# BeebOPL.net
KiCad netlist of a schematic drawn in EAGLE
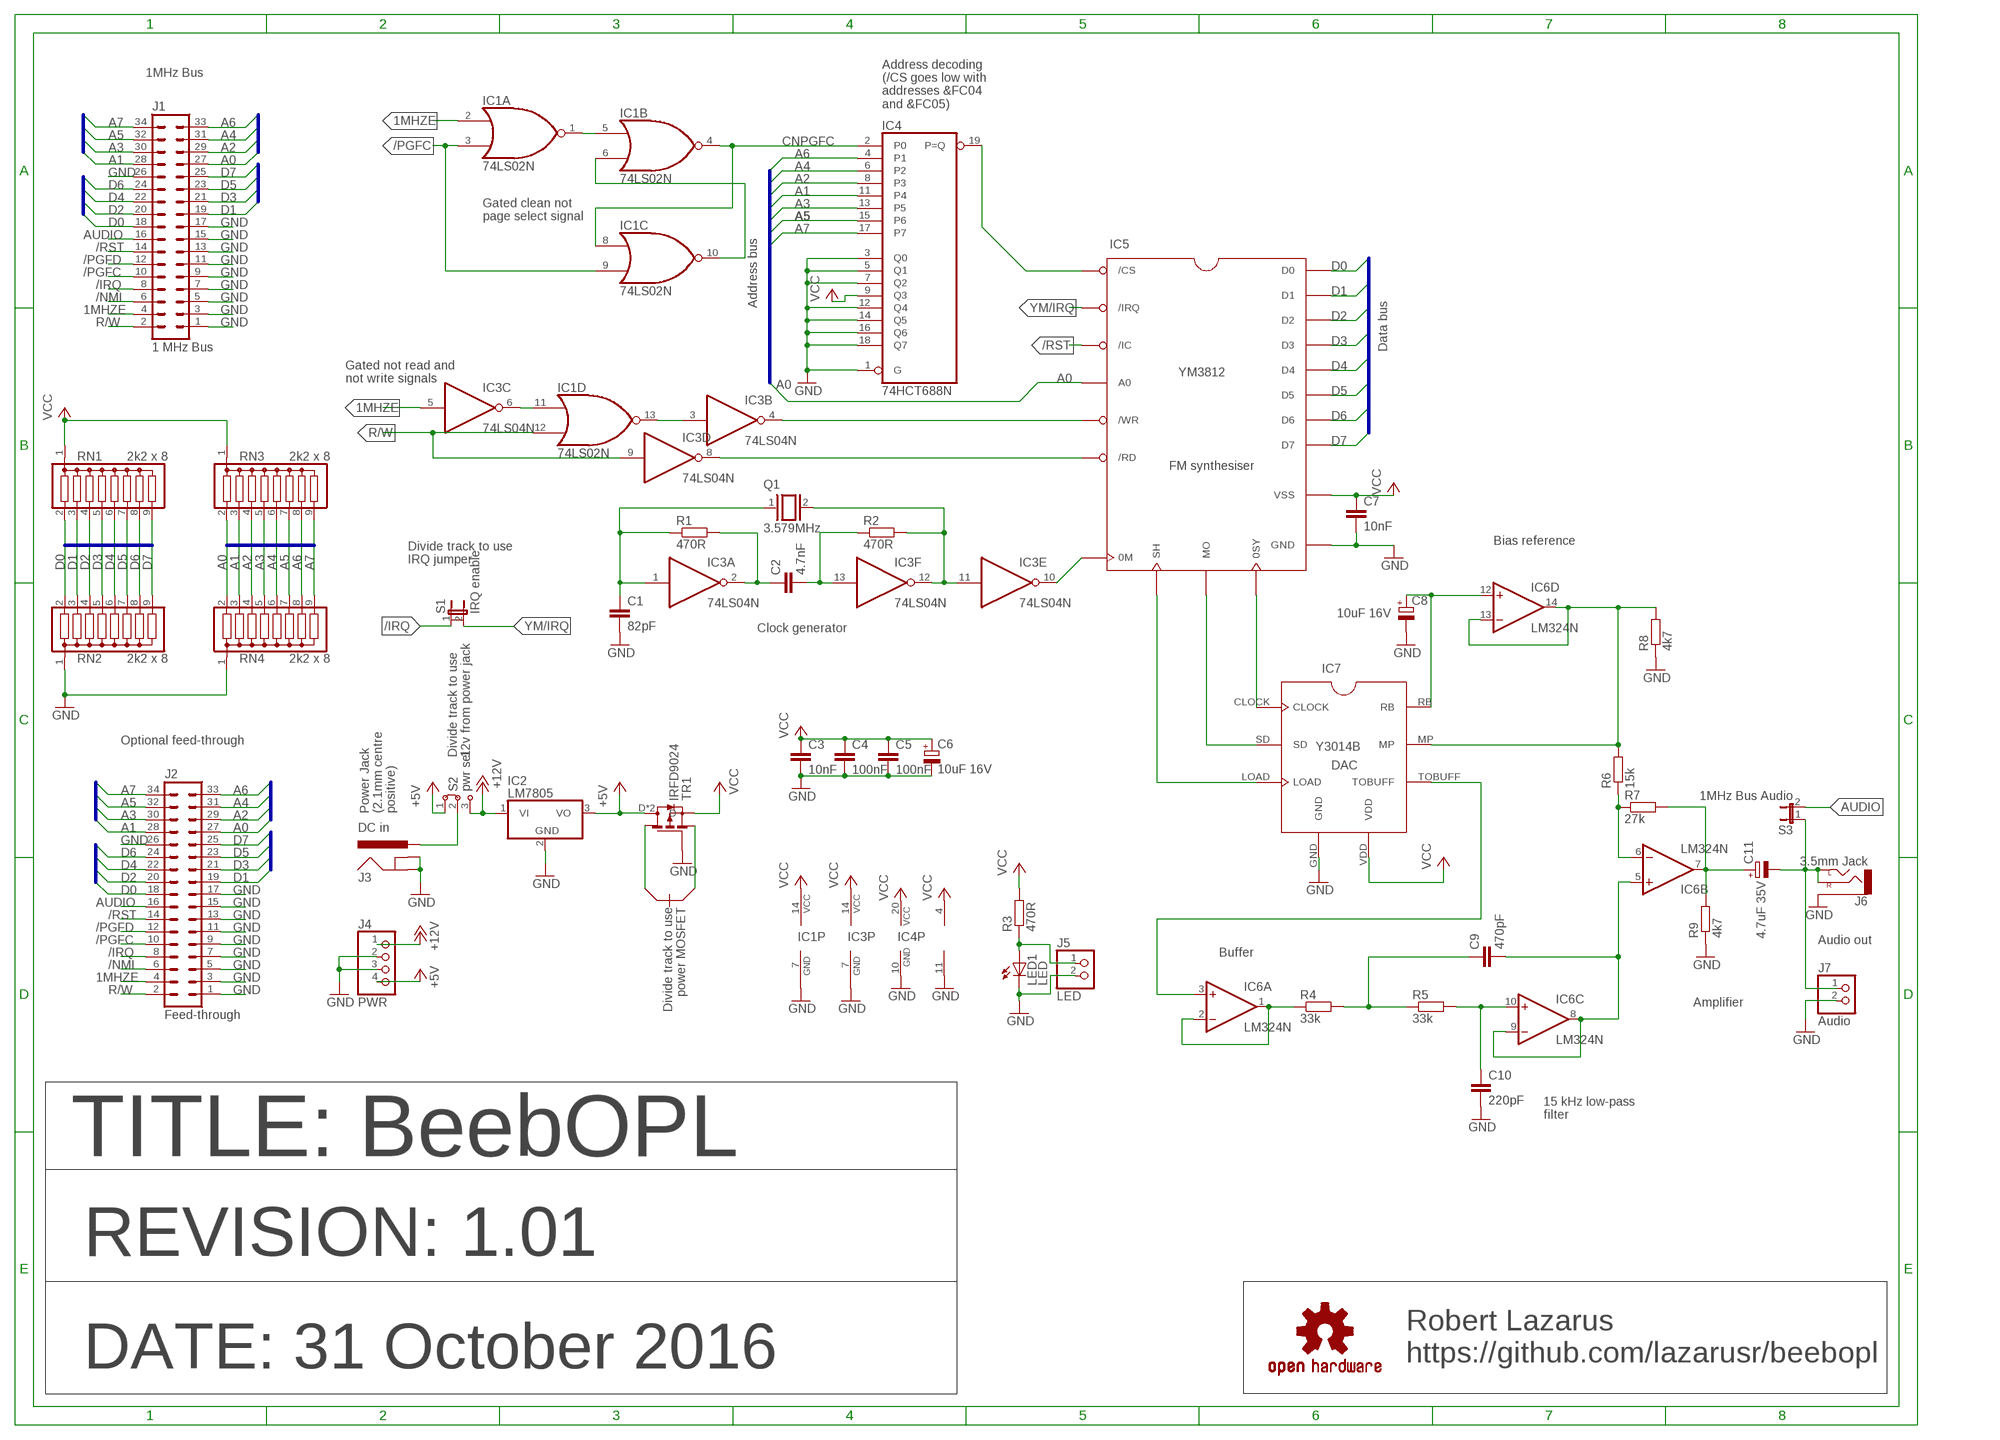
[diagram p0: schematic, sheet 1]

(export (version "E")
  (design (tool "Eeschema 10.0.6"))
  (components
    (comp (ref "C1")
      (value "82pF")
      (footprint "eagle-import:C050-024X044")
      (libsource (lib "eagle-import") (part "C-EU050-024X044"))
    )
    (comp (ref "C2")
      (value "4.7nF")
      (footprint "eagle-import:C050-024X044")
      (libsource (lib "eagle-import") (part "C-EU050-024X044"))
    )
    (comp (ref "C3")
      (value "10nF")
      (footprint "eagle-import:C050-024X044")
      (libsource (lib "eagle-import") (part "C-EU050-024X044"))
    )
    (comp (ref "C4")
      (value "100nF")
      (footprint "eagle-import:C050-024X044")
      (libsource (lib "eagle-import") (part "C-EU050-024X044"))
    )
    (comp (ref "C5")
      (value "100nF")
      (footprint "eagle-import:C050-024X044")
      (libsource (lib "eagle-import") (part "C-EU050-024X044"))
    )
    (comp (ref "C6")
      (value "10uF 16V")
      (footprint "eagle-import:E2,5-5")
      (libsource (lib "eagle-import") (part "CPOL-EUE2.5-5"))
    )
    (comp (ref "C7")
      (value "10nF")
      (footprint "eagle-import:C050-024X044")
      (libsource (lib "eagle-import") (part "C-EU050-024X044"))
    )
    (comp (ref "C8")
      (value "10uF 16V")
      (footprint "eagle-import:E2,5-5")
      (libsource (lib "eagle-import") (part "CPOL-EUE2.5-5"))
    )
    (comp (ref "C9")
      (value "470pF")
      (footprint "eagle-import:C050-024X044")
      (libsource (lib "eagle-import") (part "C-EU050-024X044"))
    )
    (comp (ref "C10")
      (value "220pF")
      (footprint "eagle-import:C050-024X044")
      (libsource (lib "eagle-import") (part "C-EU050-024X044"))
    )
    (comp (ref "C11")
      (value "4.7uF 35V")
      (footprint "eagle-import:E2,5-5")
      (libsource (lib "eagle-import") (part "CPOL-EUE2.5-5"))
    )
    (comp (ref "IC1")
      (value "74LS02N")
      (footprint "eagle-import:DIL14")
      (libsource (lib "eagle-import") (part "7402NLS"))
    )
    (comp (ref "IC2")
      (value "LM7805")
      (footprint "eagle-import:TO220V")
      (libsource (lib "eagle-import") (part "78TV05"))
    )
    (comp (ref "IC3")
      (value "74LS04N")
      (footprint "eagle-import:DIL14")
      (libsource (lib "eagle-import") (part "7404NLS"))
    )
    (comp (ref "IC4")
      (value "74HCT688N")
      (footprint "eagle-import:DIL20")
      (libsource (lib "eagle-import") (part "74688NHCT"))
    )
    (comp (ref "IC5")
      (value "YM3812")
      (footprint "eagle-import:YM3812")
      (libsource (lib "eagle-import") (part "YM3812-DIP24"))
    )
    (comp (ref "IC6")
      (value "LM324N")
      (footprint "eagle-import:DIL14")
      (libsource (lib "eagle-import") (part "LM324N"))
    )
    (comp (ref "IC7")
      (value "Y3014B")
      (footprint "eagle-import:YM3014B")
      (libsource (lib "eagle-import") (part "YM3014B-DIP8"))
    )
    (comp (ref "J1")
      (value "1 MHz Bus")
      (footprint "eagle-import:ML34")
      (libsource (lib "eagle-import") (part "ML34"))
    )
    (comp (ref "J2")
      (value "Feed-through")
      (footprint "eagle-import:ML34")
      (libsource (lib "eagle-import") (part "ML34"))
    )
    (comp (ref "J3")
      (value "DC in")
      (footprint "eagle-import:POWER_JACK_SLOT")
      (libsource (lib "eagle-import") (part "POWER_JACKSLT"))
    )
    (comp (ref "J4")
      (value "PWR")
      (footprint "eagle-import:1X04")
      (libsource (lib "eagle-import") (part "PINHD-1X4"))
    )
    (comp (ref "J5")
      (value "LED")
      (footprint "eagle-import:1X02")
      (libsource (lib "eagle-import") (part "PINHD-1X2"))
    )
    (comp (ref "J6")
      (value "3.5mm Jack")
      (footprint "eagle-import:AUDIO-JACK")
      (libsource (lib "eagle-import") (part "AUDIO-JACKPTH"))
    )
    (comp (ref "J7")
      (value "Audio")
      (footprint "eagle-import:1X02")
      (libsource (lib "eagle-import") (part "PINHD-1X2"))
    )
    (comp (ref "LED1")
      (value "LED")
      (footprint "eagle-import:LED5MM")
      (libsource (lib "eagle-import") (part "LED5MM"))
    )
    (comp (ref "LOGO1")
      (value "OSHW-LOGO-BOTTOML")
      (footprint "eagle-import:OSHW-LOGO-L")
      (libsource (lib "eagle-import") (part "OSHW-LOGO-BOTTOML"))
    )
    (comp (ref "Q1")
      (value "3.579MHz")
      (footprint "eagle-import:QS")
      (libsource (lib "eagle-import") (part "XTAL/S"))
    )
    (comp (ref "R1")
      (value "470R")
      (footprint "eagle-import:0207_10")
      (libsource (lib "eagle-import") (part "R-EU_0207/10"))
    )
    (comp (ref "R2")
      (value "470R")
      (footprint "eagle-import:0207_10")
      (libsource (lib "eagle-import") (part "R-EU_0207/10"))
    )
    (comp (ref "R3")
      (value "470R")
      (footprint "eagle-import:0207_10")
      (libsource (lib "eagle-import") (part "R-EU_0207/10"))
    )
    (comp (ref "R4")
      (value "33k")
      (footprint "eagle-import:0207_10")
      (libsource (lib "eagle-import") (part "R-EU_0207/10"))
    )
    (comp (ref "R5")
      (value "33k")
      (footprint "eagle-import:0207_10")
      (libsource (lib "eagle-import") (part "R-EU_0207/10"))
    )
    (comp (ref "R6")
      (value "15k")
      (footprint "eagle-import:0207_10")
      (libsource (lib "eagle-import") (part "R-EU_0207/10"))
    )
    (comp (ref "R7")
      (value "27k")
      (footprint "eagle-import:0207_10")
      (libsource (lib "eagle-import") (part "R-EU_0207/10"))
    )
    (comp (ref "R8")
      (value "4k7")
      (footprint "eagle-import:0207_10")
      (libsource (lib "eagle-import") (part "R-EU_0207/10"))
    )
    (comp (ref "R9")
      (value "4k7")
      (footprint "eagle-import:0207_10")
      (libsource (lib "eagle-import") (part "R-EU_0207/10"))
    )
    (comp (ref "RN1")
      (value "2k2 x 8")
      (footprint "eagle-import:SIL9")
      (libsource (lib "eagle-import") (part "G08R"))
    )
    (comp (ref "RN2")
      (value "2k2 x 8")
      (footprint "eagle-import:SIL9")
      (libsource (lib "eagle-import") (part "G08R"))
    )
    (comp (ref "RN3")
      (value "2k2 x 8")
      (footprint "eagle-import:SIL9")
      (libsource (lib "eagle-import") (part "G08R"))
    )
    (comp (ref "RN4")
      (value "2k2 x 8")
      (footprint "eagle-import:SIL9")
      (libsource (lib "eagle-import") (part "G08R"))
    )
    (comp (ref "S1")
      (value "IRQ enable")
      (footprint "eagle-import:1X02")
      (libsource (lib "eagle-import") (part "YMSynth_JUMPER-2PTH"))
    )
    (comp (ref "S2")
      (value "pwr sel")
      (footprint "eagle-import:S_3WAY_OR")
      (libsource (lib "eagle-import") (part "J2"))
    )
    (comp (ref "S3")
      (value "1MHz Bus Audio")
      (footprint "eagle-import:1X02")
      (libsource (lib "eagle-import") (part "JUMPER-2PTH"))
    )
    (comp (ref "TR1")
      (value "IRFD9024")
      (footprint "eagle-import:FET-DIL-OPTN")
      (libsource (lib "eagle-import") (part "IRFD9024-OPTN"))
    )
  )
  (nets
    (net (code "1") (name "+5V") (class "Default")
      (node (ref "IC2") (pin "3") (pinfunction "VO_3") (pintype "passive"))
      (node (ref "J4") (pin "4") (pinfunction "4_4") (pintype "passive"))
      (node (ref "S2") (pin "1") (pinfunction "1_1") (pintype "passive"))
      (node (ref "TR1") (pin "D") (pinfunction "D_D") (pintype "passive"))
      (node (ref "TR1") (pin "D1") (pinfunction "D_D1") (pintype "passive"))
    )
    (net (code "2") (name "+12V") (class "Default")
      (node (ref "IC2") (pin "1") (pinfunction "VI_1") (pintype "input"))
      (node (ref "J4") (pin "1") (pinfunction "1_1") (pintype "passive"))
      (node (ref "S2") (pin "3") (pinfunction "3_3") (pintype "passive"))
    )
    (net (code "3") (name "/A0") (class "Default")
      (node (ref "IC5") (pin "A0") (pinfunction "A0_A0") (pintype "bidirectional"))
      (node (ref "J1") (pin "27") (pinfunction "27_27") (pintype "passive"))
      (node (ref "J2") (pin "27") (pinfunction "27_27") (pintype "passive"))
      (node (ref "RN3") (pin "2") (pinfunction "2_2") (pintype "passive"))
      (node (ref "RN4") (pin "2") (pinfunction "2_2") (pintype "passive"))
    )
    (net (code "4") (name "/A1") (class "Default")
      (node (ref "IC4") (pin "11") (pinfunction "P4_11") (pintype "input"))
      (node (ref "J1") (pin "28") (pinfunction "28_28") (pintype "passive"))
      (node (ref "J2") (pin "28") (pinfunction "28_28") (pintype "passive"))
      (node (ref "RN3") (pin "3") (pinfunction "3_3") (pintype "passive"))
      (node (ref "RN4") (pin "3") (pinfunction "3_3") (pintype "passive"))
    )
    (net (code "5") (name "/A2") (class "Default")
      (node (ref "IC4") (pin "8") (pinfunction "P3_8") (pintype "input"))
      (node (ref "J1") (pin "29") (pinfunction "29_29") (pintype "passive"))
      (node (ref "J2") (pin "29") (pinfunction "29_29") (pintype "passive"))
      (node (ref "RN3") (pin "4") (pinfunction "4_4") (pintype "passive"))
      (node (ref "RN4") (pin "4") (pinfunction "4_4") (pintype "passive"))
    )
    (net (code "6") (name "/A3") (class "Default")
      (node (ref "IC4") (pin "13") (pinfunction "P5_13") (pintype "input"))
      (node (ref "J1") (pin "30") (pinfunction "30_30") (pintype "passive"))
      (node (ref "J2") (pin "30") (pinfunction "30_30") (pintype "passive"))
      (node (ref "RN3") (pin "5") (pinfunction "5_5") (pintype "passive"))
      (node (ref "RN4") (pin "5") (pinfunction "5_5") (pintype "passive"))
    )
    (net (code "7") (name "/A4") (class "Default")
      (node (ref "IC4") (pin "6") (pinfunction "P2_6") (pintype "input"))
      (node (ref "J1") (pin "31") (pinfunction "31_31") (pintype "passive"))
      (node (ref "J2") (pin "31") (pinfunction "31_31") (pintype "passive"))
      (node (ref "RN3") (pin "6") (pinfunction "6_6") (pintype "passive"))
      (node (ref "RN4") (pin "6") (pinfunction "6_6") (pintype "passive"))
    )
    (net (code "8") (name "/A5") (class "Default")
      (node (ref "IC4") (pin "15") (pinfunction "P6_15") (pintype "input"))
      (node (ref "J1") (pin "32") (pinfunction "32_32") (pintype "passive"))
      (node (ref "J2") (pin "32") (pinfunction "32_32") (pintype "passive"))
      (node (ref "RN3") (pin "7") (pinfunction "7_7") (pintype "passive"))
      (node (ref "RN4") (pin "7") (pinfunction "7_7") (pintype "passive"))
    )
    (net (code "9") (name "/A6") (class "Default")
      (node (ref "IC4") (pin "4") (pinfunction "P1_4") (pintype "input"))
      (node (ref "J1") (pin "33") (pinfunction "33_33") (pintype "passive"))
      (node (ref "J2") (pin "33") (pinfunction "33_33") (pintype "passive"))
      (node (ref "RN3") (pin "8") (pinfunction "8_8") (pintype "passive"))
      (node (ref "RN4") (pin "8") (pinfunction "8_8") (pintype "passive"))
    )
    (net (code "10") (name "/A7") (class "Default")
      (node (ref "IC4") (pin "17") (pinfunction "P7_17") (pintype "input"))
      (node (ref "J1") (pin "34") (pinfunction "34_34") (pintype "passive"))
      (node (ref "J2") (pin "34") (pinfunction "34_34") (pintype "passive"))
      (node (ref "RN3") (pin "9") (pinfunction "9_9") (pintype "passive"))
      (node (ref "RN4") (pin "9") (pinfunction "9_9") (pintype "passive"))
    )
    (net (code "11") (name "/CNPGFC") (class "Default")
      (node (ref "IC1") (pin "4") (pinfunction "O_4") (pintype "output"))
      (node (ref "IC1") (pin "8") (pinfunction "I0_8") (pintype "input"))
      (node (ref "IC4") (pin "2") (pinfunction "P0_2") (pintype "input"))
    )
    (net (code "12") (name "/D0") (class "Default")
      (node (ref "IC5") (pin "D0") (pinfunction "D0_D0") (pintype "power_in"))
      (node (ref "J1") (pin "18") (pinfunction "18_18") (pintype "passive"))
      (node (ref "J2") (pin "18") (pinfunction "18_18") (pintype "passive"))
      (node (ref "RN1") (pin "2") (pinfunction "2_2") (pintype "passive"))
      (node (ref "RN2") (pin "2") (pinfunction "2_2") (pintype "passive"))
    )
    (net (code "13") (name "/D1") (class "Default")
      (node (ref "IC5") (pin "D1") (pinfunction "D1_D1") (pintype "power_in"))
      (node (ref "J1") (pin "19") (pinfunction "19_19") (pintype "passive"))
      (node (ref "J2") (pin "19") (pinfunction "19_19") (pintype "passive"))
      (node (ref "RN1") (pin "3") (pinfunction "3_3") (pintype "passive"))
      (node (ref "RN2") (pin "3") (pinfunction "3_3") (pintype "passive"))
    )
    (net (code "14") (name "/D2") (class "Default")
      (node (ref "IC5") (pin "D2") (pinfunction "D2_D2") (pintype "power_in"))
      (node (ref "J1") (pin "20") (pinfunction "20_20") (pintype "passive"))
      (node (ref "J2") (pin "20") (pinfunction "20_20") (pintype "passive"))
      (node (ref "RN1") (pin "4") (pinfunction "4_4") (pintype "passive"))
      (node (ref "RN2") (pin "4") (pinfunction "4_4") (pintype "passive"))
    )
    (net (code "15") (name "/D3") (class "Default")
      (node (ref "IC5") (pin "D3") (pinfunction "D3_D3") (pintype "power_in"))
      (node (ref "J1") (pin "21") (pinfunction "21_21") (pintype "passive"))
      (node (ref "J2") (pin "21") (pinfunction "21_21") (pintype "passive"))
      (node (ref "RN1") (pin "5") (pinfunction "5_5") (pintype "passive"))
      (node (ref "RN2") (pin "5") (pinfunction "5_5") (pintype "passive"))
    )
    (net (code "16") (name "/D4") (class "Default")
      (node (ref "IC5") (pin "D4") (pinfunction "D4_D4") (pintype "power_in"))
      (node (ref "J1") (pin "22") (pinfunction "22_22") (pintype "passive"))
      (node (ref "J2") (pin "22") (pinfunction "22_22") (pintype "passive"))
      (node (ref "RN1") (pin "6") (pinfunction "6_6") (pintype "passive"))
      (node (ref "RN2") (pin "6") (pinfunction "6_6") (pintype "passive"))
    )
    (net (code "17") (name "/D5") (class "Default")
      (node (ref "IC5") (pin "D5") (pinfunction "D5_D5") (pintype "power_in"))
      (node (ref "J1") (pin "23") (pinfunction "23_23") (pintype "passive"))
      (node (ref "J2") (pin "23") (pinfunction "23_23") (pintype "passive"))
      (node (ref "RN1") (pin "7") (pinfunction "7_7") (pintype "passive"))
      (node (ref "RN2") (pin "7") (pinfunction "7_7") (pintype "passive"))
    )
    (net (code "18") (name "/D6") (class "Default")
      (node (ref "IC5") (pin "D6") (pinfunction "D6_D6") (pintype "power_in"))
      (node (ref "J1") (pin "24") (pinfunction "24_24") (pintype "passive"))
      (node (ref "J2") (pin "24") (pinfunction "24_24") (pintype "passive"))
      (node (ref "RN1") (pin "8") (pinfunction "8_8") (pintype "passive"))
      (node (ref "RN2") (pin "8") (pinfunction "8_8") (pintype "passive"))
    )
    (net (code "19") (name "/D7") (class "Default")
      (node (ref "IC5") (pin "D7") (pinfunction "D7_D7") (pintype "power_in"))
      (node (ref "J1") (pin "25") (pinfunction "25_25") (pintype "passive"))
      (node (ref "J2") (pin "25") (pinfunction "25_25") (pintype "passive"))
      (node (ref "RN1") (pin "9") (pinfunction "9_9") (pintype "passive"))
      (node (ref "RN2") (pin "9") (pinfunction "9_9") (pintype "passive"))
    )
    (net (code "20") (name "/{slash}NMI") (class "Default")
      (node (ref "J1") (pin "6") (pinfunction "6_6") (pintype "passive"))
      (node (ref "J2") (pin "6") (pinfunction "6_6") (pintype "passive"))
    )
    (net (code "21") (name "/{slash}PGFD") (class "Default")
      (node (ref "J1") (pin "12") (pinfunction "12_12") (pintype "passive"))
      (node (ref "J2") (pin "12") (pinfunction "12_12") (pintype "passive"))
    )
    (net (code "22") (name "1MHZE") (class "Default")
      (node (ref "IC1") (pin "2") (pinfunction "I0_2") (pintype "input"))
      (node (ref "IC3") (pin "5") (pinfunction "I_5") (pintype "input"))
      (node (ref "J1") (pin "4") (pinfunction "4_4") (pintype "passive"))
      (node (ref "J2") (pin "4") (pinfunction "4_4") (pintype "passive"))
    )
    (net (code "23") (name "AUDIO") (class "Default")
      (node (ref "J1") (pin "16") (pinfunction "16_16") (pintype "passive"))
      (node (ref "J2") (pin "16") (pinfunction "16_16") (pintype "passive"))
      (node (ref "S3") (pin "2") (pinfunction "2_2") (pintype "passive"))
    )
    (net (code "24") (name "GND") (class "Default")
      (node (ref "C1") (pin "2") (pinfunction "2_2") (pintype "passive"))
      (node (ref "C10") (pin "2") (pinfunction "2_2") (pintype "passive"))
      (node (ref "C3") (pin "2") (pinfunction "2_2") (pintype "passive"))
      (node (ref "C4") (pin "2") (pinfunction "2_2") (pintype "passive"))
      (node (ref "C5") (pin "2") (pinfunction "2_2") (pintype "passive"))
      (node (ref "C6") (pin "-") (pinfunction "-_-") (pintype "passive"))
      (node (ref "C7") (pin "2") (pinfunction "2_2") (pintype "passive"))
      (node (ref "C8") (pin "-") (pinfunction "-_-") (pintype "passive"))
      (node (ref "IC1") (pin "7") (pinfunction "GND_7") (pintype "power_in"))
      (node (ref "IC2") (pin "2") (pinfunction "GND_2") (pintype "passive"))
      (node (ref "IC3") (pin "7") (pinfunction "GND_7") (pintype "power_in"))
      (node (ref "IC4") (pin "1") (pinfunction "G_1") (pintype "input"))
      (node (ref "IC4") (pin "10") (pinfunction "GND_10") (pintype "power_in"))
      (node (ref "IC4") (pin "12") (pinfunction "Q4_12") (pintype "input"))
      (node (ref "IC4") (pin "14") (pinfunction "Q5_14") (pintype "input"))
      (node (ref "IC4") (pin "16") (pinfunction "Q6_16") (pintype "input"))
      (node (ref "IC4") (pin "18") (pinfunction "Q7_18") (pintype "input"))
      (node (ref "IC4") (pin "3") (pinfunction "Q0_3") (pintype "input"))
      (node (ref "IC4") (pin "5") (pinfunction "Q1_5") (pintype "input"))
      (node (ref "IC4") (pin "7") (pinfunction "Q2_7") (pintype "input"))
      (node (ref "IC5") (pin "GND") (pinfunction "GND_GND") (pintype "power_in"))
      (node (ref "IC6") (pin "11") (pinfunction "V-_11") (pintype "power_in"))
      (node (ref "IC7") (pin "GND") (pinfunction "GND_GND") (pintype "power_in"))
      (node (ref "J1") (pin "1") (pinfunction "1_1") (pintype "passive"))
      (node (ref "J1") (pin "11") (pinfunction "11_11") (pintype "passive"))
      (node (ref "J1") (pin "13") (pinfunction "13_13") (pintype "passive"))
      (node (ref "J1") (pin "15") (pinfunction "15_15") (pintype "passive"))
      (node (ref "J1") (pin "17") (pinfunction "17_17") (pintype "passive"))
      (node (ref "J1") (pin "26") (pinfunction "26_26") (pintype "passive"))
      (node (ref "J1") (pin "3") (pinfunction "3_3") (pintype "passive"))
      (node (ref "J1") (pin "5") (pinfunction "5_5") (pintype "passive"))
      (node (ref "J1") (pin "7") (pinfunction "7_7") (pintype "passive"))
      (node (ref "J1") (pin "9") (pinfunction "9_9") (pintype "passive"))
      (node (ref "J2") (pin "1") (pinfunction "1_1") (pintype "passive"))
      (node (ref "J2") (pin "11") (pinfunction "11_11") (pintype "passive"))
      (node (ref "J2") (pin "13") (pinfunction "13_13") (pintype "passive"))
      (node (ref "J2") (pin "15") (pinfunction "15_15") (pintype "passive"))
      (node (ref "J2") (pin "17") (pinfunction "17_17") (pintype "passive"))
      (node (ref "J2") (pin "26") (pinfunction "26_26") (pintype "passive"))
      (node (ref "J2") (pin "3") (pinfunction "3_3") (pintype "passive"))
      (node (ref "J2") (pin "5") (pinfunction "5_5") (pintype "passive"))
      (node (ref "J2") (pin "7") (pinfunction "7_7") (pintype "passive"))
      (node (ref "J2") (pin "9") (pinfunction "9_9") (pintype "passive"))
      (node (ref "J3") (pin "GND@1") (pinfunction "GNDBREAK_GND@1") (pintype "bidirectional"))
      (node (ref "J3") (pin "GND@2") (pinfunction "GND_GND@2") (pintype "bidirectional"))
      (node (ref "J4") (pin "2") (pinfunction "2_2") (pintype "passive"))
      (node (ref "J4") (pin "3") (pinfunction "3_3") (pintype "passive"))
      (node (ref "J5") (pin "2") (pinfunction "2_2") (pintype "passive"))
      (node (ref "J6") (pin "SLEEVE") (pinfunction "SLEEVE_SLEEVE") (pintype "bidirectional"))
      (node (ref "J7") (pin "2") (pinfunction "2_2") (pintype "passive"))
      (node (ref "LED1") (pin "K") (pinfunction "C_K") (pintype "passive"))
      (node (ref "R8") (pin "1") (pinfunction "1_1") (pintype "passive"))
      (node (ref "R9") (pin "1") (pinfunction "1_1") (pintype "passive"))
      (node (ref "RN2") (pin "1") (pinfunction "1_1") (pintype "passive"))
      (node (ref "RN4") (pin "1") (pinfunction "1_1") (pintype "passive"))
      (node (ref "TR1") (pin "G") (pinfunction "G_G") (pintype "passive"))
    )
    (net (code "25") (name "Net-(C9-Pad1)") (class "Default")
      (node (ref "C9") (pin "1") (pinfunction "1_1") (pintype "passive"))
      (node (ref "R4") (pin "2") (pinfunction "2_2") (pintype "passive"))
      (node (ref "R5") (pin "1") (pinfunction "1_1") (pintype "passive"))
    )
    (net (code "26") (name "Net-(IC1A-O)") (class "Default")
      (node (ref "IC1") (pin "1") (pinfunction "O_1") (pintype "output"))
      (node (ref "IC1") (pin "5") (pinfunction "I0_5") (pintype "input"))
    )
    (net (code "27") (name "Net-(IC1B-I1)") (class "Default")
      (node (ref "IC1") (pin "10") (pinfunction "O_10") (pintype "output"))
      (node (ref "IC1") (pin "6") (pinfunction "I1_6") (pintype "input"))
    )
    (net (code "28") (name "Net-(IC1D-I0)") (class "Default")
      (node (ref "IC1") (pin "11") (pinfunction "I0_11") (pintype "input"))
      (node (ref "IC3") (pin "6") (pinfunction "O_6") (pintype "output"))
    )
    (net (code "29") (name "Net-(IC1D-O)") (class "Default")
      (node (ref "IC1") (pin "13") (pinfunction "O_13") (pintype "output"))
      (node (ref "IC3") (pin "3") (pinfunction "I_3") (pintype "input"))
    )
    (net (code "30") (name "Net-(IC3A-I)") (class "Default")
      (node (ref "C1") (pin "1") (pinfunction "1_1") (pintype "passive"))
      (node (ref "IC3") (pin "1") (pinfunction "I_1") (pintype "input"))
      (node (ref "Q1") (pin "1") (pinfunction "1_1") (pintype "passive"))
      (node (ref "R1") (pin "1") (pinfunction "1_1") (pintype "passive"))
    )
    (net (code "31") (name "Net-(IC3A-O)") (class "Default")
      (node (ref "C2") (pin "1") (pinfunction "1_1") (pintype "passive"))
      (node (ref "IC3") (pin "2") (pinfunction "O_2") (pintype "output"))
      (node (ref "R1") (pin "2") (pinfunction "2_2") (pintype "passive"))
    )
    (net (code "32") (name "Net-(IC3B-O)") (class "Default")
      (node (ref "IC3") (pin "4") (pinfunction "O_4") (pintype "output"))
      (node (ref "IC5") (pin "/WR") (pinfunction "/WR_/WR") (pintype "bidirectional"))
    )
    (net (code "33") (name "Net-(IC3D-O)") (class "Default")
      (node (ref "IC3") (pin "8") (pinfunction "O_8") (pintype "output"))
      (node (ref "IC5") (pin "/RD") (pinfunction "/RD_/RD") (pintype "bidirectional"))
    )
    (net (code "34") (name "Net-(IC3E-I)") (class "Default")
      (node (ref "IC3") (pin "11") (pinfunction "I_11") (pintype "input"))
      (node (ref "IC3") (pin "12") (pinfunction "O_12") (pintype "output"))
      (node (ref "Q1") (pin "2") (pinfunction "2_2") (pintype "passive"))
      (node (ref "R2") (pin "2") (pinfunction "2_2") (pintype "passive"))
    )
    (net (code "35") (name "Net-(IC3E-O)") (class "Default")
      (node (ref "IC3") (pin "10") (pinfunction "O_10") (pintype "output"))
      (node (ref "IC5") (pin "0M") (pinfunction "0M_0M") (pintype "bidirectional"))
    )
    (net (code "36") (name "Net-(IC3F-I)") (class "Default")
      (node (ref "C2") (pin "2") (pinfunction "2_2") (pintype "passive"))
      (node (ref "IC3") (pin "13") (pinfunction "I_13") (pintype "input"))
      (node (ref "R2") (pin "1") (pinfunction "1_1") (pintype "passive"))
    )
    (net (code "37") (name "Net-(IC4A-P=Q)") (class "Default")
      (node (ref "IC4") (pin "19") (pinfunction "P=Q_19") (pintype "output"))
      (node (ref "IC5") (pin "/CS") (pinfunction "/CS_/CS") (pintype "bidirectional"))
    )
    (net (code "38") (name "Net-(IC5-Pad0SY)") (class "Default")
      (node (ref "IC5") (pin "0SY") (pinfunction "0SY_0SY") (pintype "bidirectional"))
      (node (ref "IC7") (pin "CLOCK") (pinfunction "CLOCK_CLOCK") (pintype "bidirectional"))
    )
    (net (code "39") (name "Net-(IC5-PadMO)") (class "Default")
      (node (ref "IC5") (pin "MO") (pinfunction "MO_MO") (pintype "bidirectional"))
      (node (ref "IC7") (pin "SD") (pinfunction "SD_SD") (pintype "bidirectional"))
    )
    (net (code "40") (name "Net-(IC5-PadSH)") (class "Default")
      (node (ref "IC5") (pin "SH") (pinfunction "SH_SH") (pintype "bidirectional"))
      (node (ref "IC7") (pin "LOAD") (pinfunction "LOAD_LOAD") (pintype "bidirectional"))
    )
    (net (code "41") (name "Net-(IC6A-+IN)") (class "Default")
      (node (ref "IC6") (pin "3") (pinfunction "+IN_3") (pintype "input"))
      (node (ref "IC7") (pin "TOBUFF") (pinfunction "TOBUFF_TOBUFF") (pintype "bidirectional"))
    )
    (net (code "42") (name "Net-(IC6A--IN)") (class "Default")
      (node (ref "IC6") (pin "1") (pinfunction "OUT_1") (pintype "output"))
      (node (ref "IC6") (pin "2") (pinfunction "-IN_2") (pintype "input"))
      (node (ref "R4") (pin "1") (pinfunction "1_1") (pintype "passive"))
    )
    (net (code "43") (name "Net-(IC6B-+IN)") (class "Default")
      (node (ref "C9") (pin "2") (pinfunction "2_2") (pintype "passive"))
      (node (ref "IC6") (pin "5") (pinfunction "+IN_5") (pintype "input"))
      (node (ref "IC6") (pin "8") (pinfunction "OUT_8") (pintype "output"))
      (node (ref "IC6") (pin "9") (pinfunction "-IN_9") (pintype "input"))
    )
    (net (code "44") (name "Net-(IC6B--IN)") (class "Default")
      (node (ref "IC6") (pin "6") (pinfunction "-IN_6") (pintype "input"))
      (node (ref "R6") (pin "1") (pinfunction "1_1") (pintype "passive"))
      (node (ref "R7") (pin "1") (pinfunction "1_1") (pintype "passive"))
    )
    (net (code "45") (name "Net-(IC6B-OUT)") (class "Default")
      (node (ref "C11") (pin "+") (pinfunction "+_+") (pintype "passive"))
      (node (ref "IC6") (pin "7") (pinfunction "OUT_7") (pintype "output"))
      (node (ref "R7") (pin "2") (pinfunction "2_2") (pintype "passive"))
      (node (ref "R9") (pin "2") (pinfunction "2_2") (pintype "passive"))
    )
    (net (code "46") (name "Net-(IC6C-+IN)") (class "Default")
      (node (ref "C10") (pin "1") (pinfunction "1_1") (pintype "passive"))
      (node (ref "IC6") (pin "10") (pinfunction "+IN_10") (pintype "input"))
      (node (ref "R5") (pin "2") (pinfunction "2_2") (pintype "passive"))
    )
    (net (code "47") (name "Net-(IC6D-+IN)") (class "Default")
      (node (ref "C8") (pin "+") (pinfunction "+_+") (pintype "passive"))
      (node (ref "IC6") (pin "12") (pinfunction "+IN_12") (pintype "input"))
      (node (ref "IC7") (pin "RB") (pinfunction "RB_RB") (pintype "bidirectional"))
    )
    (net (code "48") (name "Net-(IC6D--IN)") (class "Default")
      (node (ref "IC6") (pin "13") (pinfunction "-IN_13") (pintype "input"))
      (node (ref "IC6") (pin "14") (pinfunction "OUT_14") (pintype "output"))
      (node (ref "IC7") (pin "MP") (pinfunction "MP_MP") (pintype "bidirectional"))
      (node (ref "R6") (pin "2") (pinfunction "2_2") (pintype "passive"))
      (node (ref "R8") (pin "2") (pinfunction "2_2") (pintype "passive"))
    )
    (net (code "49") (name "Net-(J3-PadPWR)") (class "Default")
      (node (ref "J3") (pin "PWR") (pinfunction "PWR_PWR") (pintype "bidirectional"))
      (node (ref "S2") (pin "2") (pinfunction "2_2") (pintype "passive"))
    )
    (net (code "50") (name "Net-(J5-Pad1)") (class "Default")
      (node (ref "J5") (pin "1") (pinfunction "1_1") (pintype "passive"))
      (node (ref "LED1") (pin "A") (pinfunction "A_A") (pintype "passive"))
      (node (ref "R3") (pin "1") (pinfunction "1_1") (pintype "passive"))
    )
    (net (code "51") (name "Net-(J6-LEFT)") (class "Default")
      (node (ref "C11") (pin "-") (pinfunction "-_-") (pintype "passive"))
      (node (ref "J6") (pin "RING") (pinfunction "RIGHT_RING") (pintype "bidirectional"))
      (node (ref "J6") (pin "TIP") (pinfunction "LEFT_TIP") (pintype "bidirectional"))
      (node (ref "J7") (pin "1") (pinfunction "1_1") (pintype "passive"))
      (node (ref "S3") (pin "1") (pinfunction "1_1") (pintype "passive"))
    )
    (net (code "52") (name "R{slash}W") (class "Default")
      (node (ref "IC1") (pin "12") (pinfunction "I1_12") (pintype "input"))
      (node (ref "IC3") (pin "9") (pinfunction "I_9") (pintype "input"))
      (node (ref "J1") (pin "2") (pinfunction "2_2") (pintype "passive"))
      (node (ref "J2") (pin "2") (pinfunction "2_2") (pintype "passive"))
    )
    (net (code "53") (name "VCC") (class "Default")
      (node (ref "C3") (pin "1") (pinfunction "1_1") (pintype "passive"))
      (node (ref "C4") (pin "1") (pinfunction "1_1") (pintype "passive"))
      (node (ref "C5") (pin "1") (pinfunction "1_1") (pintype "passive"))
      (node (ref "C6") (pin "+") (pinfunction "+_+") (pintype "passive"))
      (node (ref "C7") (pin "1") (pinfunction "1_1") (pintype "passive"))
      (node (ref "IC1") (pin "14") (pinfunction "VCC_14") (pintype "power_in"))
      (node (ref "IC3") (pin "14") (pinfunction "VCC_14") (pintype "power_in"))
      (node (ref "IC4") (pin "20") (pinfunction "VCC_20") (pintype "power_in"))
      (node (ref "IC4") (pin "9") (pinfunction "Q3_9") (pintype "input"))
      (node (ref "IC5") (pin "VSS") (pinfunction "VSS_VSS") (pintype "power_in"))
      (node (ref "IC6") (pin "4") (pinfunction "V+_4") (pintype "power_in"))
      (node (ref "IC7") (pin "VDD") (pinfunction "VDD_VDD") (pintype "power_in"))
      (node (ref "R3") (pin "2") (pinfunction "2_2") (pintype "passive"))
      (node (ref "RN1") (pin "1") (pinfunction "1_1") (pintype "passive"))
      (node (ref "RN3") (pin "1") (pinfunction "1_1") (pintype "passive"))
      (node (ref "TR1") (pin "S") (pinfunction "S_S") (pintype "passive"))
    )
    (net (code "54") (name "YM{slash}IRQ") (class "Default")
      (node (ref "IC5") (pin "/IRQ") (pinfunction "/IRQ_/IRQ") (pintype "bidirectional"))
      (node (ref "S1") (pin "2") (pinfunction "2_2") (pintype "passive"))
    )
    (net (code "55") (name "{slash}IRQ") (class "Default")
      (node (ref "J1") (pin "8") (pinfunction "8_8") (pintype "passive"))
      (node (ref "J2") (pin "8") (pinfunction "8_8") (pintype "passive"))
      (node (ref "S1") (pin "1") (pinfunction "1_1") (pintype "passive"))
    )
    (net (code "56") (name "{slash}PGFC") (class "Default")
      (node (ref "IC1") (pin "3") (pinfunction "I1_3") (pintype "input"))
      (node (ref "IC1") (pin "9") (pinfunction "I1_9") (pintype "input"))
      (node (ref "J1") (pin "10") (pinfunction "10_10") (pintype "passive"))
      (node (ref "J2") (pin "10") (pinfunction "10_10") (pintype "passive"))
    )
    (net (code "57") (name "{slash}RST") (class "Default")
      (node (ref "IC5") (pin "/IC") (pinfunction "/IC_/IC") (pintype "bidirectional"))
      (node (ref "J1") (pin "14") (pinfunction "14_14") (pintype "passive"))
      (node (ref "J2") (pin "14") (pinfunction "14_14") (pintype "passive"))
    )
  )
)
